# MacSet-L-V2_0_0_3.net
KiCad netlist of a schematic drawn in Altium Designer
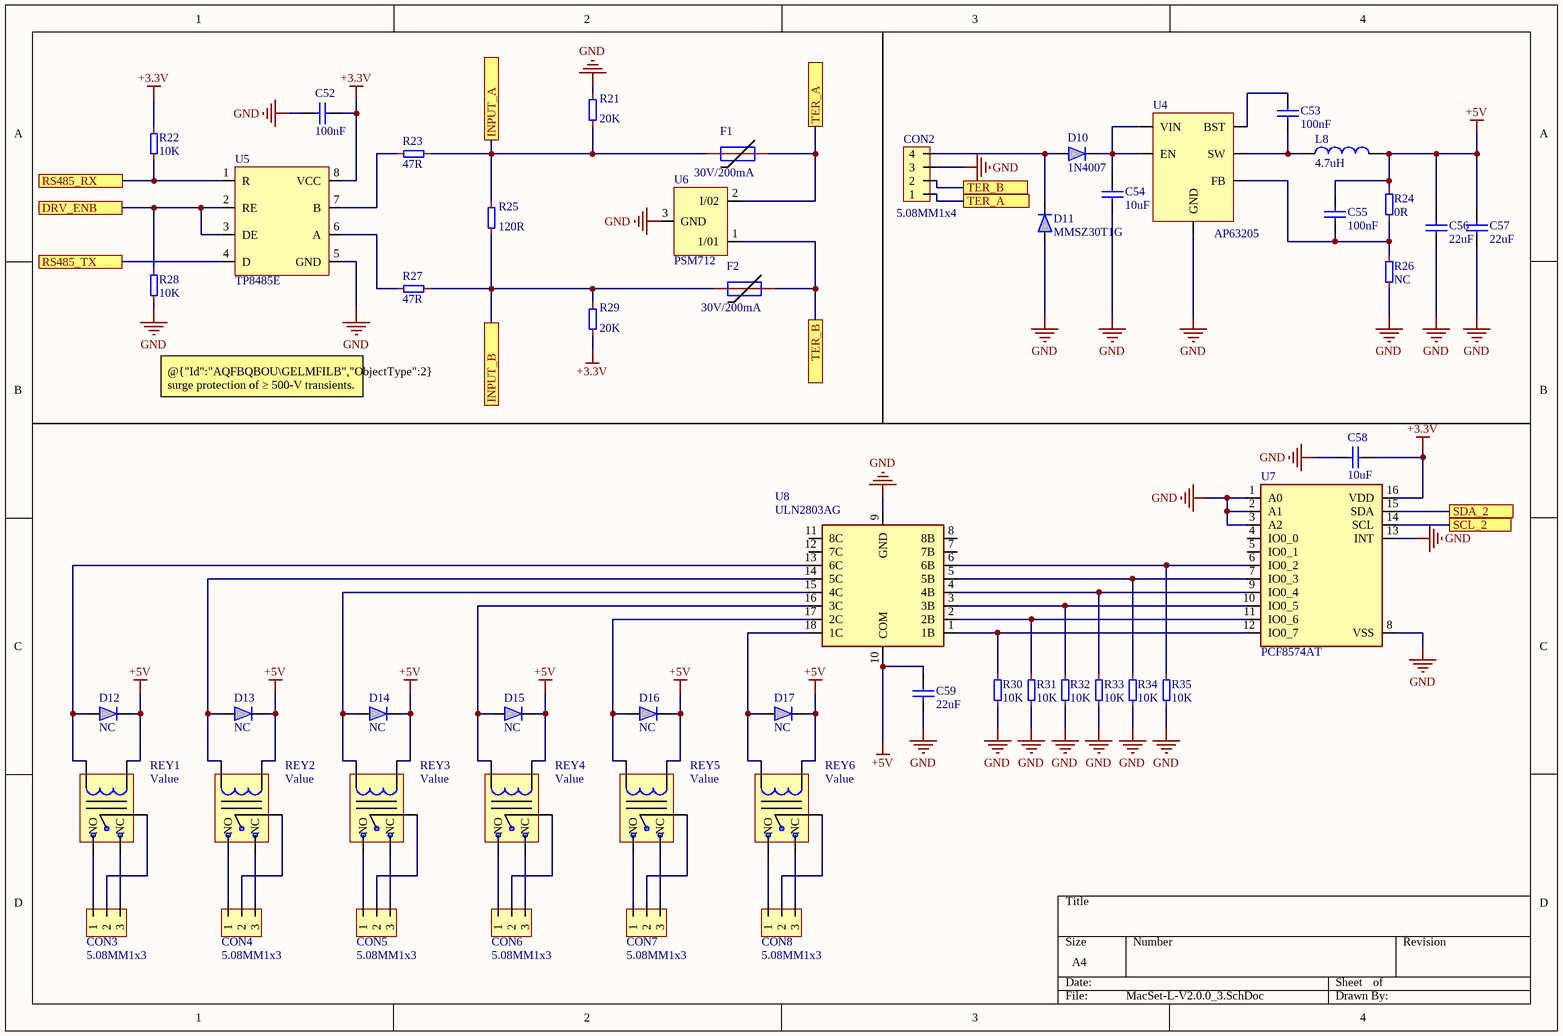
[diagram p0: MacSet-L-V2.0.0_3.SchDoc]

(export (version "E")
  (design (tool "Eeschema 10.0.6"))
  (components
    (comp (ref "C52")
      (value "100nF")
      (footprint "CAP0402")
      (description "Ceramic Capacitor X7R 0402 100nF 16V")
      (fields
        (field (name "MANUFACTURER_PART_NUMBER") "GRM155R71C104JA88D")
        (field (name "MANUFACTURER") "MURATA")
      )
      (libsource (lib "macnman_2.0") (part "Capa_0402"))
    )
    (comp (ref "C53")
      (value "100nF")
      (footprint "CAP0402")
      (description "Ceramic Capacitor C0G, NP0 0402 100nF 35V")
      (fields
        (field (name "MANUFACTURER_PART_NUMBER") "GRM155R61A104KA01J")
        (field (name "MANUFACTURER") "MURATA")
      )
      (libsource (lib "macnman_2.0") (part "Capa_0402"))
    )
    (comp (ref "C54")
      (value "10uF")
      (footprint "CAP0805")
      (description "MLCC - SMD/SMT 10 uF 50VDC 10% 0805 X6S")
      (fields
        (field (name "MANUFACTURER_PART_NUMBER") "CC0805KKX5R9BB106")
        (field (name "MANUFACTURER") "YAGEO")
      )
      (libsource (lib "macnman_2.0") (part "Capa_0805"))
    )
    (comp (ref "C55")
      (value "100nF")
      (footprint "CAP0402")
      (description "Ceramic Capacitor C0G, NP0 0402 100nF 35V")
      (fields
        (field (name "MANUFACTURER_PART_NUMBER") "GRM155R61A104KA01J")
        (field (name "MANUFACTURER") "MURATA")
      )
      (libsource (lib "macnman_2.0") (part "Capa_0402"))
    )
    (comp (ref "C56")
      (value "22uF")
      (footprint "CAP0805")
      (description "MLCC - SMD/SMT 22uF 10VDC 20% 0805 X6S")
      (fields
        (field (name "MANUFACTURER_PART_NUMBER") "CC0805KKX7R6BB226")
        (field (name "MANUFACTURER") "YAGEO")
      )
      (libsource (lib "macnman_2.0") (part "Capa_0805"))
    )
    (comp (ref "C57")
      (value "22uF")
      (footprint "CAP0805")
      (description "MLCC - SMD/SMT 22uF 10VDC 20% 0805 X6S")
      (fields
        (field (name "MANUFACTURER_PART_NUMBER") "CC0805KKX7R6BB226")
        (field (name "MANUFACTURER") "MURATA")
      )
      (libsource (lib "macnman_2.0") (part "Capa_0805"))
    )
    (comp (ref "C58")
      (value "10uF")
      (footprint "CAP0603")
      (description "Ceramic Capacitor X5R 0603 10uF 10V")
      (fields
        (field (name "MANUFACTURER_PART_NUMBER") "CL10A106KP8NNNL")
        (field (name "MANUFACTURER") "SAMSUNG")
      )
      (libsource (lib "macnman_2.0") (part "CAP_0603"))
    )
    (comp (ref "C59")
      (value "22uF")
      (footprint "CAP0805")
      (description "MLCC - SMD/SMT 22uF 10VDC 20% 0805 X6S")
      (fields
        (field (name "MANUFACTURER_PART_NUMBER") "CC0805KKX7R6BB226")
        (field (name "MANUFACTURER") "MURATA")
      )
      (libsource (lib "macnman_2.0") (part "Capa_0805"))
    )
    (comp (ref "CON2")
      (value "5.08MM1x4")
      (footprint "Screw Terminal Block 5.08x4")
      (description "5.08mm 1*4 Screw Terminal Block")
      (fields (field (name "MANUFACTURER") "XINYA"))
      (libsource (lib "macnman_2.0") (part "Screw Terminal Block 4x1 5.08mm"))
    )
    (comp (ref "CON3")
      (value "5.08MM1x3")
      (footprint "Screw Terminal Block 5.08x3")
      (description "5.08mm 1*3 Screw Terminal Block")
      (fields (field (name "MANUFACTURER_PART_NUMBER") "XY302V-3.5-3P") (field (name "MANUFACTURER") "XINYA"))
      (libsource (lib "macnman_2.0") (part "Screw Terminal Block 3x1 5.08mm"))
    )
    (comp (ref "CON4")
      (value "5.08MM1x3")
      (footprint "Screw Terminal Block 5.08x3")
      (description "5.08mm 1*3 Screw Terminal Block")
      (fields (field (name "MANUFACTURER_PART_NUMBER") "XY302V-3.5-3P") (field (name "MANUFACTURER") "XINYA"))
      (libsource (lib "macnman_2.0") (part "Screw Terminal Block 3x1 5.08mm"))
    )
    (comp (ref "CON5")
      (value "5.08MM1x3")
      (footprint "Screw Terminal Block 5.08x3")
      (description "5.08mm 1*3 Screw Terminal Block")
      (fields (field (name "MANUFACTURER_PART_NUMBER") "XY302V-3.5-3P") (field (name "MANUFACTURER") "XINYA"))
      (libsource (lib "macnman_2.0") (part "Screw Terminal Block 3x1 5.08mm"))
    )
    (comp (ref "CON6")
      (value "5.08MM1x3")
      (footprint "Screw Terminal Block 5.08x3")
      (description "5.08mm 1*3 Screw Terminal Block")
      (fields (field (name "MANUFACTURER_PART_NUMBER") "XY302V-3.5-3P") (field (name "MANUFACTURER") "XINYA"))
      (libsource (lib "macnman_2.0") (part "Screw Terminal Block 3x1 5.08mm"))
    )
    (comp (ref "CON7")
      (value "5.08MM1x3")
      (footprint "Screw Terminal Block 5.08x3")
      (description "5.08mm 1*3 Screw Terminal Block")
      (fields (field (name "MANUFACTURER_PART_NUMBER") "XY302V-3.5-3P") (field (name "MANUFACTURER") "XINYA"))
      (libsource (lib "macnman_2.0") (part "Screw Terminal Block 3x1 5.08mm"))
    )
    (comp (ref "CON8")
      (value "5.08MM1x3")
      (footprint "Screw Terminal Block 5.08x3")
      (description "5.08mm 1*3 Screw Terminal Block")
      (fields (field (name "MANUFACTURER_PART_NUMBER") "XY302V-3.5-3P") (field (name "MANUFACTURER") "XINYA"))
      (libsource (lib "macnman_2.0") (part "Screw Terminal Block 3x1 5.08mm"))
    )
    (comp (ref "D10")
      (value "1N4007")
      (footprint "Diode SMD 214AC")
      (description "Diode 1N4007 AO214AC")
      (fields (field (name "MANUFACTURER") "GENERIC"))
      (libsource (lib "macnman_2.0") (part "DIODE"))
    )
    (comp (ref "D11")
      (value "MMSZ30T1G")
      (footprint "SOD123-2")
      (description "MMSZ30T1G 30V 500mW Schottky Diodes & Rectifiers")
      (fields (field (name "MANUFACTURER") "Onsemi"))
      (libsource (lib "macnman_2.0") (part "BAT54T1G"))
    )
    (comp (ref "D12")
      (value "NC")
      (footprint "Diode SMD 214AC")
      (description "Diode 1N4007 AO214AC")
      (fields (field (name "MANUFACTURER_PART_NUMBER") "1N4007") (field (name "MANUFACTURER") "GENERIC"))
      (libsource (lib "macnman_2.0") (part "DIODE"))
    )
    (comp (ref "D13")
      (value "NC")
      (footprint "Diode SMD 214AC")
      (description "Diode 1N4007 AO214AC")
      (fields (field (name "MANUFACTURER_PART_NUMBER") "1N4007") (field (name "MANUFACTURER") "GENERIC"))
      (libsource (lib "macnman_2.0") (part "DIODE"))
    )
    (comp (ref "D14")
      (value "NC")
      (footprint "Diode SMD 214AC")
      (description "Diode 1N4007 AO214AC")
      (fields (field (name "MANUFACTURER_PART_NUMBER") "1N4007") (field (name "MANUFACTURER") "GENERIC"))
      (libsource (lib "macnman_2.0") (part "DIODE"))
    )
    (comp (ref "D15")
      (value "NC")
      (footprint "Diode SMD 214AC")
      (description "Diode 1N4007 AO214AC")
      (fields (field (name "MANUFACTURER_PART_NUMBER") "1N4007") (field (name "MANUFACTURER") "GENERIC"))
      (libsource (lib "macnman_2.0") (part "DIODE"))
    )
    (comp (ref "D16")
      (value "NC")
      (footprint "Diode SMD 214AC")
      (description "Diode 1N4007 AO214AC")
      (fields (field (name "MANUFACTURER_PART_NUMBER") "1N4007") (field (name "MANUFACTURER") "GENERIC"))
      (libsource (lib "macnman_2.0") (part "DIODE"))
    )
    (comp (ref "D17")
      (value "NC")
      (footprint "Diode SMD 214AC")
      (description "Diode 1N4007 AO214AC")
      (fields (field (name "MANUFACTURER_PART_NUMBER") "1N4007") (field (name "MANUFACTURER") "GENERIC"))
      (libsource (lib "macnman_2.0") (part "DIODE"))
    )
    (comp (ref "F1")
      (value "30V/200mA")
      (footprint "FUSE_1206")
      (description "Polymeric PTC Resettable Fuse 30V 200mA Surface Mount 1206")
      (fields
        (field (name "MANUFACTURER_PART_NUMBER") "nSMD020-30V")
        (field (name "MANUFACTURER") "TECHFUSE")
      )
      (libsource (lib "macnman_2.0") (part "FUSE_1206"))
    )
    (comp (ref "F2")
      (value "30V/200mA")
      (footprint "FUSE_1206")
      (description "Polymeric PTC Resettable Fuse 30V 200mA Surface Mount 1206")
      (fields
        (field (name "MANUFACTURER_PART_NUMBER") "nSMD020-30V")
        (field (name "MANUFACTURER") "TECHFUSE")
      )
      (libsource (lib "macnman_2.0") (part "FUSE_1206"))
    )
    (comp (ref "L8")
      (value "4.7uH")
      (footprint "IND_3x3x1.5MM")
      (description "1.09A 4.7uH ±3% 163mΩ 3015 Inductors")
      (fields
        (field (name "MANUFACTURER_PART_NUMBER") "SWPA3015S4R7MT")
        (field (name "MANUFACTURER") "SUNLORD")
      )
      (libsource (lib "macnman_2.0") (part "INDUCTOR"))
    )
    (comp (ref "R21")
      (value "20K")
      (footprint "RESC0402")
      (description "Resistor SMD 0402")
      (fields
        (field (name "MANUFACTURER_PART_NUMBER") "CRCW040220K0FKEDC")
        (field (name "MANUFACTURER") "YAGEO")
      )
      (libsource (lib "macnman_2.0") (part "RES_0402"))
    )
    (comp (ref "R22")
      (value "10K")
      (footprint "RESC0402")
      (description "Thick Film Resistors - SMD 1/16watt 10Kohms 0402 1% Commercial Use")
      (fields
        (field (name "MANUFACTURER_PART_NUMBER") "CRCW040210K0FKEDC")
        (field (name "MANUFACTURER") "Vishay")
      )
      (libsource (lib "macnman_2.0") (part "RES_0402"))
    )
    (comp (ref "R23")
      (value "47R")
      (footprint "RESC0603")
      (description "Thick Film Resistors - SMD 1/16Watt 47ohms 1% Commercial Use")
      (fields
        (field (name "MANUFACTURER_PART_NUMBER") "RC0402FR-0747RL")
        (field (name "MANUFACTURER") "Vishay")
      )
      (libsource (lib "macnman_2.0") (part "RES_0603"))
    )
    (comp (ref "R24")
      (value "0R")
      (footprint "RESC0402")
      (description "Thick Film Resistors - SMD 1/16watt 0R 1% 0402 Commercial Use")
      (fields
        (field (name "MANUFACTURER_PART_NUMBER") "RC0402FR-070RL")
        (field (name "MANUFACTURER") "Vishay")
      )
      (libsource (lib "macnman_2.0") (part "RES_0402"))
    )
    (comp (ref "R25")
      (value "120R")
      (footprint "RESC0402")
      (description "Resistor SMD 0402")
      (fields (field (name "Comment") "NC"))
      (libsource (lib "macnman_2.0") (part "RES_0402"))
    )
    (comp (ref "R26")
      (value "NC")
      (footprint "RESC0402")
      (description "Thick Film Resistors - SMD 1/16watt 10Kohms 0.1% 0402 Commercial Use")
      (fields
        (field (name "MANUFACTURER_PART_NUMBER") "MCS04020D1002BE000")
        (field (name "MANUFACTURER") "Vishay")
      )
      (libsource (lib "macnman_2.0") (part "RES_0402"))
    )
    (comp (ref "R27")
      (value "47R")
      (footprint "RESC0603")
      (description "Thick Film Resistors - SMD 1/16Watt 47ohms 1% Commercial Use")
      (fields
        (field (name "MANUFACTURER_PART_NUMBER") "RC0402FR-0747RL")
        (field (name "MANUFACTURER") "Vishay")
      )
      (libsource (lib "macnman_2.0") (part "RES_0603"))
    )
    (comp (ref "R28")
      (value "10K")
      (footprint "RESC0402")
      (description "Thick Film Resistors - SMD 1/16watt 10Kohms 0402 1% Commercial Use")
      (fields
        (field (name "MANUFACTURER_PART_NUMBER") "CRCW040210K0FKEDC")
        (field (name "MANUFACTURER") "Vishay")
      )
      (libsource (lib "macnman_2.0") (part "RES_0402"))
    )
    (comp (ref "R29")
      (value "20K")
      (footprint "RESC0402")
      (description "Resistor SMD 0402")
      (fields
        (field (name "MANUFACTURER_PART_NUMBER") "CRCW040220K0FKEDC")
        (field (name "MANUFACTURER") "YAGEO")
      )
      (libsource (lib "macnman_2.0") (part "RES_0402"))
    )
    (comp (ref "R30")
      (value "10K")
      (footprint "RESC0402")
      (description "Thick Film Resistors - SMD 1/16watt 10Kohms 0402 1% Commercial Use")
      (fields
        (field (name "MANUFACTURER_PART_NUMBER") "CRCW040210K0FKEDC")
        (field (name "MANUFACTURER") "Vishay")
      )
      (libsource (lib "macnman_2.0") (part "RES_0402"))
    )
    (comp (ref "R31")
      (value "10K")
      (footprint "RESC0402")
      (description "Thick Film Resistors - SMD 1/16watt 10Kohms 0402 1% Commercial Use")
      (fields
        (field (name "MANUFACTURER_PART_NUMBER") "CRCW040210K0FKEDC")
        (field (name "MANUFACTURER") "Vishay")
      )
      (libsource (lib "macnman_2.0") (part "RES_0402"))
    )
    (comp (ref "R32")
      (value "10K")
      (footprint "RESC0402")
      (description "Thick Film Resistors - SMD 1/16watt 10Kohms 0402 1% Commercial Use")
      (fields
        (field (name "MANUFACTURER_PART_NUMBER") "CRCW040210K0FKEDC")
        (field (name "MANUFACTURER") "Vishay")
      )
      (libsource (lib "macnman_2.0") (part "RES_0402"))
    )
    (comp (ref "R33")
      (value "10K")
      (footprint "RESC0402")
      (description "Thick Film Resistors - SMD 1/16watt 10Kohms 0402 1% Commercial Use")
      (fields
        (field (name "MANUFACTURER_PART_NUMBER") "CRCW040210K0FKEDC")
        (field (name "MANUFACTURER") "Vishay")
      )
      (libsource (lib "macnman_2.0") (part "RES_0402"))
    )
    (comp (ref "R34")
      (value "10K")
      (footprint "RESC0402")
      (description "Thick Film Resistors - SMD 1/16watt 10Kohms 0402 1% Commercial Use")
      (fields
        (field (name "MANUFACTURER_PART_NUMBER") "CRCW040210K0FKEDC")
        (field (name "MANUFACTURER") "Vishay")
      )
      (libsource (lib "macnman_2.0") (part "RES_0402"))
    )
    (comp (ref "R35")
      (value "10K")
      (footprint "RESC0402")
      (description "Thick Film Resistors - SMD 1/16watt 10Kohms 0402 1% Commercial Use")
      (fields
        (field (name "MANUFACTURER_PART_NUMBER") "CRCW040210K0FKEDC")
        (field (name "MANUFACTURER") "Vishay")
      )
      (libsource (lib "macnman_2.0") (part "RES_0402"))
    )
    (comp (ref "REY1")
      (value "Value")
      (footprint "Relay")
      (description "5V Sugar Cube Relay 44mA")
      (libsource (lib "macnman_2.0") (part "Relay"))
    )
    (comp (ref "REY2")
      (value "Value")
      (footprint "Relay")
      (description "5V Sugar Cube Relay 44mA")
      (libsource (lib "macnman_2.0") (part "Relay"))
    )
    (comp (ref "REY3")
      (value "Value")
      (footprint "Relay")
      (description "5V Sugar Cube Relay 44mA")
      (libsource (lib "macnman_2.0") (part "Relay"))
    )
    (comp (ref "REY4")
      (value "Value")
      (footprint "Relay")
      (description "5V Sugar Cube Relay 44mA")
      (libsource (lib "macnman_2.0") (part "Relay"))
    )
    (comp (ref "REY5")
      (value "Value")
      (footprint "Relay")
      (description "5V Sugar Cube Relay 44mA")
      (libsource (lib "macnman_2.0") (part "Relay"))
    )
    (comp (ref "REY6")
      (value "Value")
      (footprint "Relay")
      (description "5V Sugar Cube Relay 44mA")
      (libsource (lib "macnman_2.0") (part "Relay"))
    )
    (comp (ref "U4")
      (value "AP63205")
      (footprint "SOT23-6")
      (description "AP63205 - Switching Voltage Regulators 5V OUT DCDC 3.8V-32V Conv HV Buck TSOT26 T&R 3K")
      (fields
        (field (name "MANUFACTURER_PART_NUMBER") "AP63205QWU-7")
        (field (name "MANUFACTURER") "Diodes Incorporated")
      )
      (libsource (lib "macnman_2.0") (part "AP63205"))
    )
    (comp (ref "U5")
      (value "TP8485E")
      (footprint "SOIC8")
      (description "TP8485E RS485 Tranreciver 3V-5.5V SOIC8")
      (fields (field (name "MANUFACTURER") "3PEAK") (field (name "MANUFACTURER_PART_NUMBER") "TP8485"))
      (libsource (lib "macnman_2.0") (part "TP8485E"))
    )
    (comp (ref "U6")
      (value "PSM712")
      (footprint "SOT23")
      (description "Asymmerical TVS Diode for Extended Common-Mode RS-485")
      (fields
        (field (name "MANUFACTURER_PART_NUMBER") "SM712H-TP-B002")
        (field (name "MANUFACTURER") "Micro Commercial Components (MCC)")
      )
      (libsource (lib "macnman_2.0") (part "PSM712"))
    )
    (comp (ref "U7")
      (value "PCF8574AT")
      (footprint "SOIC-16-W")
      (description "PCF8574AT 8Bit I2C GPIO Expander 16 Pin")
      (fields (field (name "MANUFACTURER") "NXP Semiconductors"))
      (libsource (lib "macnman_2.0") (part "PCF8574AT"))
    )
    (comp (ref "U8")
      (value "ULN2803AG")
      (footprint "SOIC-18-W")
      (description "ULN2803C device is a 50V, 500mA Darlington\r\ntransistor array")
      (fields (field (name "MANUFACTURER_PART_NUMBER") "ULN2803A") (field (name "MANUFACTURER") "UMW"))
      (libsource (lib "macnman_2.0") (part "ULN2803AG"))
    )
  )
  (nets
    (net (code "1") (name "+3.3V") (class "Default")
      (node (ref "C52") (pin "2") (pinfunction "2_2") (pintype "passive"))
      (node (ref "C58") (pin "2") (pinfunction "2_2") (pintype "passive"))
      (node (ref "R22") (pin "2") (pinfunction "2_2") (pintype "passive"))
      (node (ref "R29") (pin "1") (pinfunction "1_1") (pintype "passive"))
      (node (ref "U5") (pin "8") (pinfunction "VCC_8") (pintype "passive"))
      (node (ref "U7") (pin "16") (pinfunction "VDD_16") (pintype "passive"))
    )
    (net (code "2") (name "+5V") (class "Default")
      (node (ref "C55") (pin "2") (pinfunction "2_2") (pintype "passive"))
      (node (ref "C56") (pin "2") (pinfunction "2_2") (pintype "passive"))
      (node (ref "C57") (pin "2") (pinfunction "2_2") (pintype "passive"))
      (node (ref "C59") (pin "1") (pinfunction "1_1") (pintype "passive"))
      (node (ref "D12") (pin "1") (pinfunction "K_1") (pintype "passive"))
      (node (ref "D13") (pin "1") (pinfunction "K_1") (pintype "passive"))
      (node (ref "D14") (pin "1") (pinfunction "K_1") (pintype "passive"))
      (node (ref "D15") (pin "1") (pinfunction "K_1") (pintype "passive"))
      (node (ref "D16") (pin "1") (pinfunction "K_1") (pintype "passive"))
      (node (ref "D17") (pin "1") (pinfunction "K_1") (pintype "passive"))
      (node (ref "L8") (pin "2") (pintype "passive"))
      (node (ref "R24") (pin "1") (pinfunction "1_1") (pintype "passive"))
      (node (ref "REY1") (pin "1") (pinfunction "+_1") (pintype "passive"))
      (node (ref "REY2") (pin "1") (pinfunction "+_1") (pintype "passive"))
      (node (ref "REY3") (pin "1") (pinfunction "+_1") (pintype "passive"))
      (node (ref "REY4") (pin "1") (pinfunction "+_1") (pintype "passive"))
      (node (ref "REY5") (pin "1") (pinfunction "+_1") (pintype "passive"))
      (node (ref "REY6") (pin "1") (pinfunction "+_1") (pintype "passive"))
      (node (ref "U8") (pin "10") (pinfunction "COM_10") (pintype "passive"))
    )
    (net (code "3") (name "/DRV_ENB") (class "Default")
      (node (ref "R28") (pin "2") (pinfunction "2_2") (pintype "passive"))
      (node (ref "U5") (pin "2") (pinfunction "RE_2") (pintype "passive"))
      (node (ref "U5") (pin "3") (pinfunction "DE_3") (pintype "passive"))
    )
    (net (code "4") (name "/INPUT_A") (class "Default")
      (node (ref "F1") (pin "1") (pinfunction "49_1") (pintype "passive"))
      (node (ref "R21") (pin "1") (pinfunction "1_1") (pintype "passive"))
      (node (ref "R23") (pin "2") (pinfunction "2_2") (pintype "passive"))
      (node (ref "R25") (pin "2") (pinfunction "2_2") (pintype "passive"))
    )
    (net (code "5") (name "/INPUT_B") (class "Default")
      (node (ref "F2") (pin "1") (pinfunction "49_1") (pintype "passive"))
      (node (ref "R25") (pin "1") (pinfunction "1_1") (pintype "passive"))
      (node (ref "R27") (pin "2") (pinfunction "2_2") (pintype "passive"))
      (node (ref "R29") (pin "2") (pinfunction "2_2") (pintype "passive"))
    )
    (net (code "6") (name "/RS485_RX") (class "Default")
      (node (ref "R22") (pin "1") (pinfunction "1_1") (pintype "passive"))
      (node (ref "U5") (pin "1") (pinfunction "R_1") (pintype "passive"))
    )
    (net (code "7") (name "/RS485_TX") (class "Default")
      (node (ref "U5") (pin "4") (pinfunction "D_4") (pintype "passive"))
    )
    (net (code "8") (name "/SCL_2") (class "Default")
      (node (ref "U7") (pin "14") (pinfunction "SCL_14") (pintype "passive"))
    )
    (net (code "9") (name "/SDA_2") (class "Default")
      (node (ref "U7") (pin "15") (pinfunction "SDA_15") (pintype "passive"))
    )
    (net (code "10") (name "/TER_A") (class "Default")
      (node (ref "CON2") (pin "1") (pinfunction "1_1") (pintype "passive"))
      (node (ref "F1") (pin "2") (pinfunction "50_2") (pintype "passive"))
      (node (ref "U6") (pin "2") (pinfunction "I/02_2") (pintype "passive"))
    )
    (net (code "11") (name "/TER_B") (class "Default")
      (node (ref "CON2") (pin "2") (pinfunction "2_2") (pintype "passive"))
      (node (ref "F2") (pin "2") (pinfunction "50_2") (pintype "passive"))
      (node (ref "U6") (pin "1") (pinfunction "1/01_1") (pintype "passive"))
    )
    (net (code "12") (name "GND") (class "Default")
      (node (ref "C52") (pin "1") (pinfunction "1_1") (pintype "passive"))
      (node (ref "C54") (pin "1") (pinfunction "1_1") (pintype "passive"))
      (node (ref "C56") (pin "1") (pinfunction "1_1") (pintype "passive"))
      (node (ref "C57") (pin "1") (pinfunction "1_1") (pintype "passive"))
      (node (ref "C58") (pin "1") (pinfunction "1_1") (pintype "passive"))
      (node (ref "C59") (pin "2") (pinfunction "2_2") (pintype "passive"))
      (node (ref "CON2") (pin "3") (pinfunction "3_3") (pintype "passive"))
      (node (ref "D11") (pin "2") (pinfunction "A_2") (pintype "passive"))
      (node (ref "R21") (pin "2") (pinfunction "2_2") (pintype "passive"))
      (node (ref "R26") (pin "2") (pinfunction "2_2") (pintype "passive"))
      (node (ref "R28") (pin "1") (pinfunction "1_1") (pintype "passive"))
      (node (ref "R30") (pin "1") (pinfunction "1_1") (pintype "passive"))
      (node (ref "R31") (pin "1") (pinfunction "1_1") (pintype "passive"))
      (node (ref "R32") (pin "1") (pinfunction "1_1") (pintype "passive"))
      (node (ref "R33") (pin "1") (pinfunction "1_1") (pintype "passive"))
      (node (ref "R34") (pin "1") (pinfunction "1_1") (pintype "passive"))
      (node (ref "R35") (pin "1") (pinfunction "1_1") (pintype "passive"))
      (node (ref "U4") (pin "4") (pinfunction "GND_4") (pintype "passive"))
      (node (ref "U5") (pin "5") (pinfunction "GND_5") (pintype "passive"))
      (node (ref "U6") (pin "3") (pinfunction "GND_3") (pintype "passive"))
      (node (ref "U7") (pin "1") (pinfunction "A0_1") (pintype "power_in"))
      (node (ref "U7") (pin "13") (pinfunction "INT_13") (pintype "passive"))
      (node (ref "U7") (pin "2") (pinfunction "A1_2") (pintype "power_in"))
      (node (ref "U7") (pin "3") (pinfunction "A2_3") (pintype "passive"))
      (node (ref "U7") (pin "8") (pinfunction "VSS_8") (pintype "passive"))
      (node (ref "U8") (pin "9") (pinfunction "GND_9") (pintype "passive"))
    )
    (net (code "13") (name "Net-(D10-A)") (class "Default")
      (node (ref "CON2") (pin "4") (pinfunction "4_4") (pintype "passive"))
      (node (ref "D10") (pin "2") (pinfunction "A_2") (pintype "passive"))
      (node (ref "D11") (pin "1") (pinfunction "K_1") (pintype "passive"))
    )
    (net (code "14") (name "Net-(D10-K)") (class "Default")
      (node (ref "C54") (pin "2") (pinfunction "2_2") (pintype "passive"))
      (node (ref "D10") (pin "1") (pinfunction "K_1") (pintype "passive"))
      (node (ref "U4") (pin "2") (pinfunction "EN_2") (pintype "passive"))
      (node (ref "U4") (pin "3") (pinfunction "VIN_3") (pintype "passive"))
    )
    (net (code "15") (name "Net-(D12-A)") (class "Default")
      (node (ref "D12") (pin "2") (pinfunction "A_2") (pintype "passive"))
      (node (ref "REY1") (pin "3") (pinfunction "-_3") (pintype "passive"))
      (node (ref "U8") (pin "13") (pinfunction "6C_13") (pintype "passive"))
    )
    (net (code "16") (name "Net-(D13-A)") (class "Default")
      (node (ref "D13") (pin "2") (pinfunction "A_2") (pintype "passive"))
      (node (ref "REY2") (pin "3") (pinfunction "-_3") (pintype "passive"))
      (node (ref "U8") (pin "14") (pinfunction "5C_14") (pintype "passive"))
    )
    (net (code "17") (name "Net-(D14-A)") (class "Default")
      (node (ref "D14") (pin "2") (pinfunction "A_2") (pintype "passive"))
      (node (ref "REY3") (pin "3") (pinfunction "-_3") (pintype "passive"))
      (node (ref "U8") (pin "15") (pinfunction "4C_15") (pintype "passive"))
    )
    (net (code "18") (name "Net-(D15-A)") (class "Default")
      (node (ref "D15") (pin "2") (pinfunction "A_2") (pintype "passive"))
      (node (ref "REY4") (pin "3") (pinfunction "-_3") (pintype "passive"))
      (node (ref "U8") (pin "16") (pinfunction "3C_16") (pintype "passive"))
    )
    (net (code "19") (name "Net-(D16-A)") (class "Default")
      (node (ref "D16") (pin "2") (pinfunction "A_2") (pintype "passive"))
      (node (ref "REY5") (pin "3") (pinfunction "-_3") (pintype "passive"))
      (node (ref "U8") (pin "17") (pinfunction "2C_17") (pintype "passive"))
    )
    (net (code "20") (name "Net-(D17-A)") (class "Default")
      (node (ref "D17") (pin "2") (pinfunction "A_2") (pintype "passive"))
      (node (ref "REY6") (pin "3") (pinfunction "-_3") (pintype "passive"))
      (node (ref "U8") (pin "18") (pinfunction "1C_18") (pintype "passive"))
    )
    (net (code "21") (name "Net-(REY1-CM)") (class "Default")
      (node (ref "CON3") (pin "2") (pinfunction "2_2") (pintype "passive"))
      (node (ref "REY1") (pin "2") (pinfunction "CM_2") (pintype "passive"))
    )
    (net (code "22") (name "Net-(REY1-NC)") (class "Default")
      (node (ref "CON3") (pin "3") (pinfunction "3_3") (pintype "passive"))
      (node (ref "REY1") (pin "5") (pinfunction "NC_5") (pintype "passive"))
    )
    (net (code "23") (name "Net-(REY1-NO)") (class "Default")
      (node (ref "CON3") (pin "1") (pinfunction "1_1") (pintype "passive"))
      (node (ref "REY1") (pin "4") (pinfunction "NO_4") (pintype "passive"))
    )
    (net (code "24") (name "Net-(REY2-CM)") (class "Default")
      (node (ref "CON4") (pin "2") (pinfunction "2_2") (pintype "passive"))
      (node (ref "REY2") (pin "2") (pinfunction "CM_2") (pintype "passive"))
    )
    (net (code "25") (name "Net-(REY2-NC)") (class "Default")
      (node (ref "CON4") (pin "3") (pinfunction "3_3") (pintype "passive"))
      (node (ref "REY2") (pin "5") (pinfunction "NC_5") (pintype "passive"))
    )
    (net (code "26") (name "Net-(REY2-NO)") (class "Default")
      (node (ref "CON4") (pin "1") (pinfunction "1_1") (pintype "passive"))
      (node (ref "REY2") (pin "4") (pinfunction "NO_4") (pintype "passive"))
    )
    (net (code "27") (name "Net-(REY3-CM)") (class "Default")
      (node (ref "CON5") (pin "2") (pinfunction "2_2") (pintype "passive"))
      (node (ref "REY3") (pin "2") (pinfunction "CM_2") (pintype "passive"))
    )
    (net (code "28") (name "Net-(REY3-NC)") (class "Default")
      (node (ref "CON5") (pin "3") (pinfunction "3_3") (pintype "passive"))
      (node (ref "REY3") (pin "5") (pinfunction "NC_5") (pintype "passive"))
    )
    (net (code "29") (name "Net-(REY3-NO)") (class "Default")
      (node (ref "CON5") (pin "1") (pinfunction "1_1") (pintype "passive"))
      (node (ref "REY3") (pin "4") (pinfunction "NO_4") (pintype "passive"))
    )
    (net (code "30") (name "Net-(REY4-CM)") (class "Default")
      (node (ref "CON6") (pin "2") (pinfunction "2_2") (pintype "passive"))
      (node (ref "REY4") (pin "2") (pinfunction "CM_2") (pintype "passive"))
    )
    (net (code "31") (name "Net-(REY4-NC)") (class "Default")
      (node (ref "CON6") (pin "3") (pinfunction "3_3") (pintype "passive"))
      (node (ref "REY4") (pin "5") (pinfunction "NC_5") (pintype "passive"))
    )
    (net (code "32") (name "Net-(REY4-NO)") (class "Default")
      (node (ref "CON6") (pin "1") (pinfunction "1_1") (pintype "passive"))
      (node (ref "REY4") (pin "4") (pinfunction "NO_4") (pintype "passive"))
    )
    (net (code "33") (name "Net-(REY5-CM)") (class "Default")
      (node (ref "CON7") (pin "2") (pinfunction "2_2") (pintype "passive"))
      (node (ref "REY5") (pin "2") (pinfunction "CM_2") (pintype "passive"))
    )
    (net (code "34") (name "Net-(REY5-NC)") (class "Default")
      (node (ref "CON7") (pin "3") (pinfunction "3_3") (pintype "passive"))
      (node (ref "REY5") (pin "5") (pinfunction "NC_5") (pintype "passive"))
    )
    (net (code "35") (name "Net-(REY5-NO)") (class "Default")
      (node (ref "CON7") (pin "1") (pinfunction "1_1") (pintype "passive"))
      (node (ref "REY5") (pin "4") (pinfunction "NO_4") (pintype "passive"))
    )
    (net (code "36") (name "Net-(REY6-CM)") (class "Default")
      (node (ref "CON8") (pin "2") (pinfunction "2_2") (pintype "passive"))
      (node (ref "REY6") (pin "2") (pinfunction "CM_2") (pintype "passive"))
    )
    (net (code "37") (name "Net-(REY6-NC)") (class "Default")
      (node (ref "CON8") (pin "3") (pinfunction "3_3") (pintype "passive"))
      (node (ref "REY6") (pin "5") (pinfunction "NC_5") (pintype "passive"))
    )
    (net (code "38") (name "Net-(REY6-NO)") (class "Default")
      (node (ref "CON8") (pin "1") (pinfunction "1_1") (pintype "passive"))
      (node (ref "REY6") (pin "4") (pinfunction "NO_4") (pintype "passive"))
    )
    (net (code "39") (name "Net-(U4-BST)") (class "Default")
      (node (ref "C53") (pin "2") (pinfunction "2_2") (pintype "passive"))
      (node (ref "U4") (pin "6") (pinfunction "BST_6") (pintype "passive"))
    )
    (net (code "40") (name "Net-(U4-FB)") (class "Default")
      (node (ref "C55") (pin "1") (pinfunction "1_1") (pintype "passive"))
      (node (ref "R24") (pin "2") (pinfunction "2_2") (pintype "passive"))
      (node (ref "R26") (pin "1") (pinfunction "1_1") (pintype "passive"))
      (node (ref "U4") (pin "1") (pinfunction "FB_1") (pintype "passive"))
    )
    (net (code "41") (name "Net-(U4-SW)") (class "Default")
      (node (ref "C53") (pin "1") (pinfunction "1_1") (pintype "passive"))
      (node (ref "L8") (pin "1") (pintype "passive"))
      (node (ref "U4") (pin "5") (pinfunction "SW_5") (pintype "passive"))
    )
    (net (code "42") (name "Net-(U5-A)") (class "Default")
      (node (ref "R27") (pin "1") (pinfunction "1_1") (pintype "passive"))
      (node (ref "U5") (pin "6") (pinfunction "A_6") (pintype "passive"))
    )
    (net (code "43") (name "Net-(U5-B)") (class "Default")
      (node (ref "R23") (pin "1") (pinfunction "1_1") (pintype "passive"))
      (node (ref "U5") (pin "7") (pinfunction "B_7") (pintype "passive"))
    )
    (net (code "44") (name "Net-(U7-IO0_2)") (class "Default")
      (node (ref "R35") (pin "2") (pinfunction "2_2") (pintype "passive"))
      (node (ref "U7") (pin "6") (pinfunction "IO0_2_6") (pintype "passive"))
      (node (ref "U8") (pin "6") (pinfunction "6B_6") (pintype "passive"))
    )
    (net (code "45") (name "Net-(U7-IO0_3)") (class "Default")
      (node (ref "R34") (pin "2") (pinfunction "2_2") (pintype "passive"))
      (node (ref "U7") (pin "7") (pinfunction "IO0_3_7") (pintype "passive"))
      (node (ref "U8") (pin "5") (pinfunction "5B_5") (pintype "passive"))
    )
    (net (code "46") (name "Net-(U7-IO0_4)") (class "Default")
      (node (ref "R33") (pin "2") (pinfunction "2_2") (pintype "passive"))
      (node (ref "U7") (pin "9") (pinfunction "IO0_4_9") (pintype "passive"))
      (node (ref "U8") (pin "4") (pinfunction "4B_4") (pintype "passive"))
    )
    (net (code "47") (name "Net-(U7-IO0_5)") (class "Default")
      (node (ref "R32") (pin "2") (pinfunction "2_2") (pintype "passive"))
      (node (ref "U7") (pin "10") (pinfunction "IO0_5_10") (pintype "passive"))
      (node (ref "U8") (pin "3") (pinfunction "3B_3") (pintype "passive"))
    )
    (net (code "48") (name "Net-(U7-IO0_6)") (class "Default")
      (node (ref "R31") (pin "2") (pinfunction "2_2") (pintype "passive"))
      (node (ref "U7") (pin "11") (pinfunction "IO0_6_11") (pintype "passive"))
      (node (ref "U8") (pin "2") (pinfunction "2B_2") (pintype "power_in"))
    )
    (net (code "49") (name "Net-(U7-IO0_7)") (class "Default")
      (node (ref "R30") (pin "2") (pinfunction "2_2") (pintype "passive"))
      (node (ref "U7") (pin "12") (pinfunction "IO0_7_12") (pintype "passive"))
      (node (ref "U8") (pin "1") (pinfunction "1B_1") (pintype "power_in"))
    )
    (net (code "50") (name "unconnected-(U7-IO0_0-Pad4)") (class "Default")
      (node (ref "U7") (pin "4") (pinfunction "IO0_0_4") (pintype "passive"))
    )
    (net (code "51") (name "unconnected-(U7-IO0_1-Pad5)") (class "Default")
      (node (ref "U7") (pin "5") (pinfunction "IO0_1_5") (pintype "passive"))
    )
    (net (code "52") (name "unconnected-(U8-7B-Pad7)") (class "Default")
      (node (ref "U8") (pin "7") (pinfunction "7B_7") (pintype "passive"))
    )
    (net (code "53") (name "unconnected-(U8-7C-Pad12)") (class "Default")
      (node (ref "U8") (pin "12") (pinfunction "7C_12") (pintype "passive"))
    )
    (net (code "54") (name "unconnected-(U8-8B-Pad8)") (class "Default")
      (node (ref "U8") (pin "8") (pinfunction "8B_8") (pintype "passive"))
    )
    (net (code "55") (name "unconnected-(U8-8C-Pad11)") (class "Default")
      (node (ref "U8") (pin "11") (pinfunction "8C_11") (pintype "passive"))
    )
  )
)
